# MotorDriver.net
KiCad netlist of a schematic drawn in EAGLE
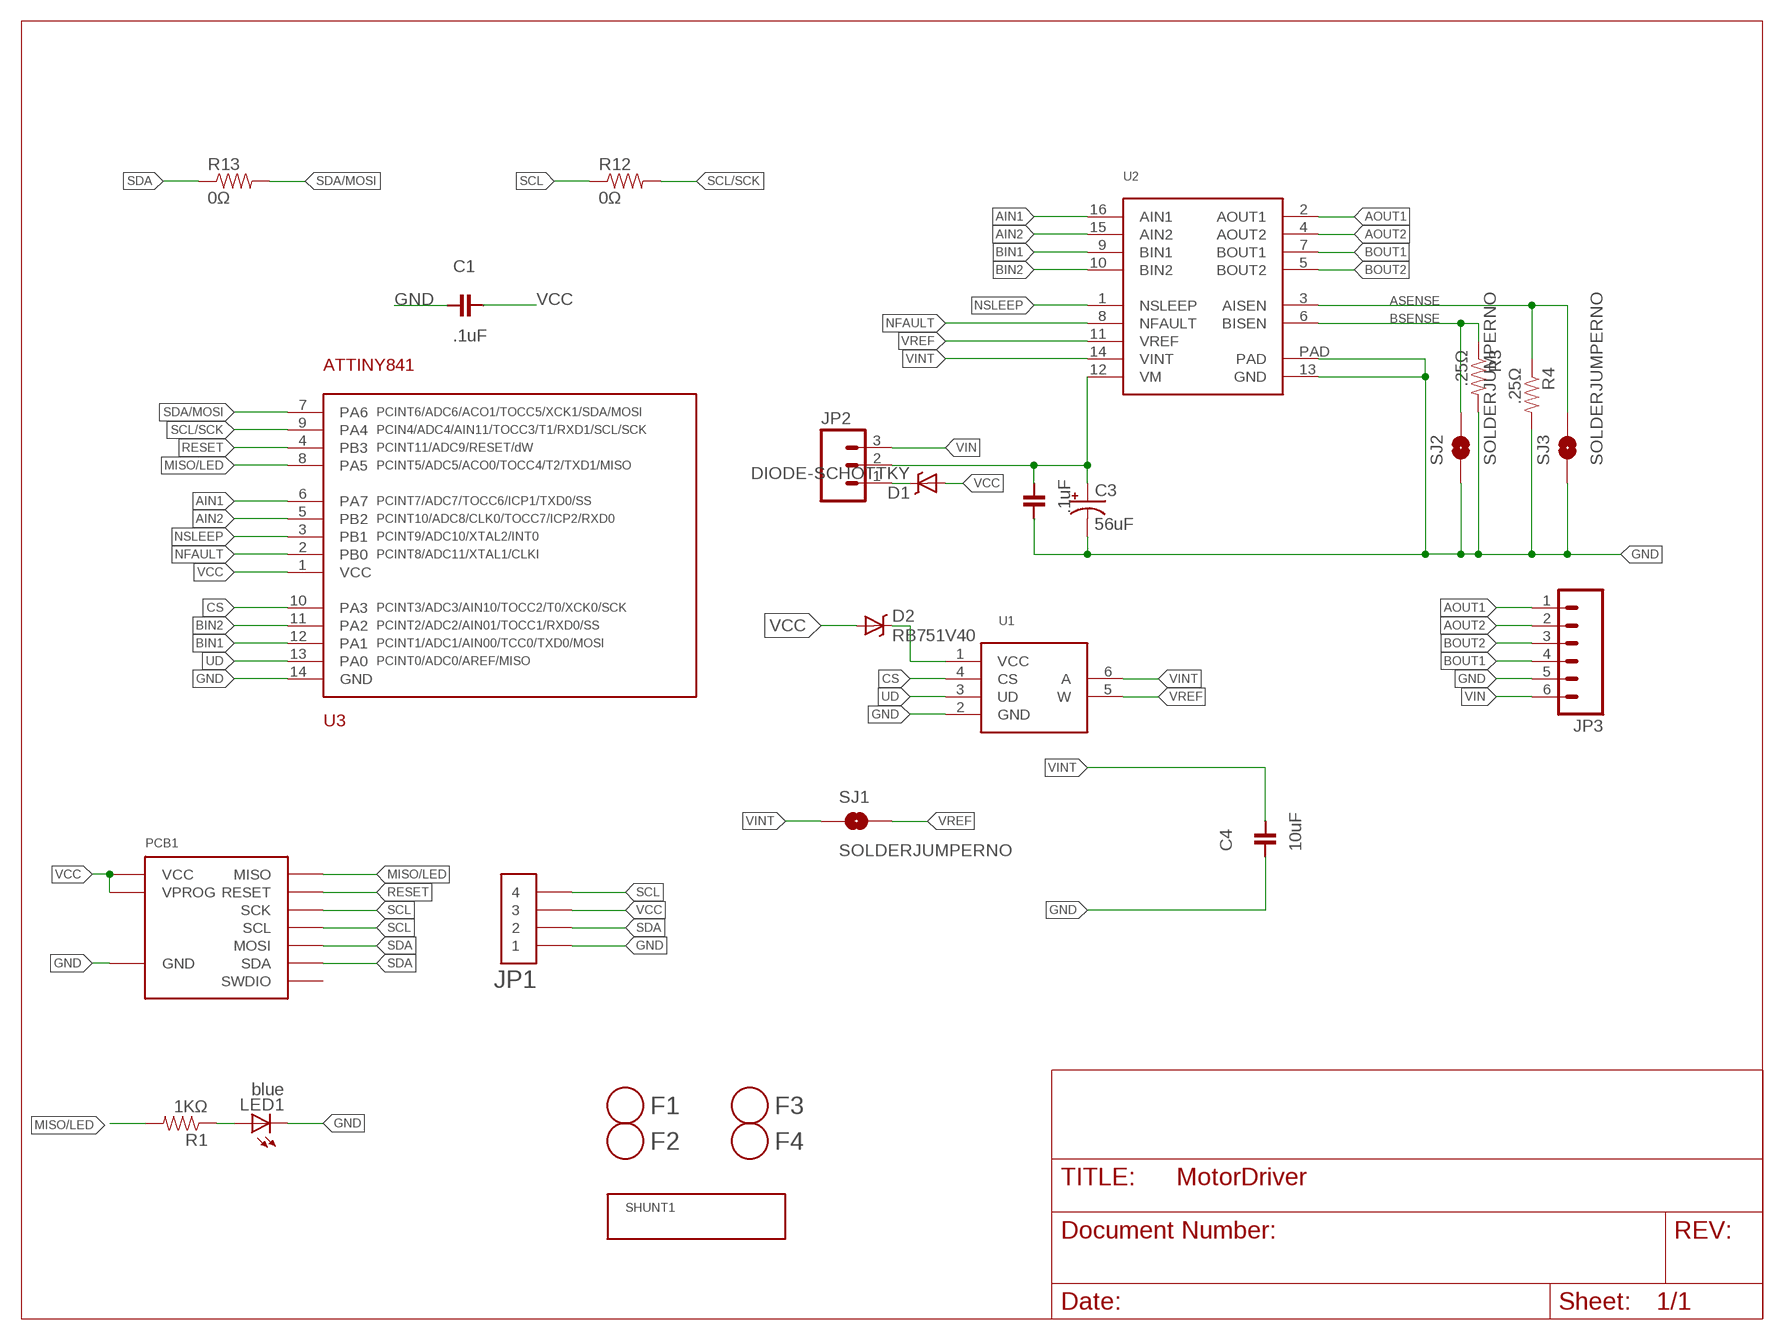
[diagram p0: schematic, sheet 1]

(export (version "E")
  (design (tool "Eeschema 10.0.6"))
  (components
    (comp (ref "C1")
      (value ".1uF")
      (footprint "eagle-import:0603")
      (fields (field (name "PARTNUM") "C0603C104K5RACTU"))
      (libsource (lib "eagle-import") (part "CAPACITOR-.1UF"))
    )
    (comp (ref "C2")
      (value ".1uF")
      (footprint "eagle-import:0603")
      (fields (field (name "PARTNUM") "C0603C104K5RACTU"))
      (libsource (lib "eagle-import") (part "CAPACITOR-.1UF"))
    )
    (comp (ref "C3")
      (value "56uF")
      (footprint "eagle-import:PANASONIC_D")
      (fields (field (name "PARTNUM") "EMVA250ADA560MF55G"))
      (libsource (lib "eagle-import") (part "CAPACITOR-POL-56UF-25V"))
    )
    (comp (ref "C4")
      (value "10uF")
      (footprint "eagle-import:0603")
      (fields (field (name "PARTNUM") "GRM188R61C106MA73D"))
      (libsource (lib "eagle-import") (part "CAPACITOR-10UF"))
    )
    (comp (ref "D1")
      (value "DIODE-SCHOTTKY")
      (footprint "eagle-import:SMP")
      (fields (field (name "PARTNUM") "SS3P3-M3/84A"))
      (libsource (lib "eagle-import") (part "DIODE-SCHOTTKY"))
    )
    (comp (ref "D2")
      (value "RB751V40")
      (footprint "eagle-import:SOD-323")
      (fields (field (name "PARTNUM") "BAT60A") (field (name "PARTNUM_1") "RB751V40"))
      (libsource (lib "eagle-import") (part "DIODE-SCHOTTKY-BAT60A"))
    )
    (comp (ref "F1")
      (value "FIDUCIAL")
      (footprint "eagle-import:FIDUCIAL_1MM")
      (libsource (lib "eagle-import") (part "FIDUCIAL"))
    )
    (comp (ref "F2")
      (value "FIDUCIAL")
      (footprint "eagle-import:FIDUCIAL_1MM")
      (libsource (lib "eagle-import") (part "FIDUCIAL"))
    )
    (comp (ref "F3")
      (value "FIDUCIAL")
      (footprint "eagle-import:FIDUCIAL_1MM")
      (libsource (lib "eagle-import") (part "FIDUCIAL"))
    )
    (comp (ref "F4")
      (value "FIDUCIAL")
      (footprint "eagle-import:FIDUCIAL_1MM")
      (libsource (lib "eagle-import") (part "FIDUCIAL"))
    )
    (comp (ref "JP1")
      (value "HEADER-1X4-AMPMODU")
      (footprint "eagle-import:AMPMODU-4P")
      (fields (field (name "PARTNUM") "147721-3"))
      (libsource (lib "eagle-import") (part "HEADER-1X4-AMPMODU"))
    )
    (comp (ref "JP2")
      (value "M03LOCK_NO_SILK")
      (footprint "eagle-import:1X03_LOCK_NO_SILK")
      (fields (field (name "PARTNUM") "M20-9990346"))
      (libsource (lib "eagle-import") (part "M03LOCK_NO_SILK"))
    )
    (comp (ref "JP3")
      (value "M063.5MM-6")
      (footprint "eagle-import:SCREWTERMINAL-3.5MM-6")
      (fields (field (name "PARTNUM") "OSTTE060104"))
      (libsource (lib "eagle-import") (part "M063.5MM-6"))
    )
    (comp (ref "LED1")
      (value "blue")
      (footprint "eagle-import:0805-LED")
      (fields (field (name "PARTNUM") "LTST-C171TBKT"))
      (libsource (lib "eagle-import") (part "LED-0805-BLUE"))
    )
    (comp (ref "PCB1")
      (value "DEVICE-PCB")
      (footprint "eagle-import:DEVICE-PCB")
      (fields (field (name "PARTNUM") "Motor Driver PCB"))
      (libsource (lib "eagle-import") (part "DEVICE-PCB"))
    )
    (comp (ref "R1")
      (value "1KΩ")
      (footprint "eagle-import:0603")
      (fields (field (name "PARTNUM") "ERJ-3EKF1001V"))
      (libsource (lib "eagle-import") (part "RESISTOR-1KΩ"))
    )
    (comp (ref "R3")
      (value ".25Ω")
      (footprint "eagle-import:R2010")
      (fields (field (name "PARTNUM") "CSRN2010FKR250"))
      (libsource (lib "eagle-import") (part "RESISTOR2010"))
    )
    (comp (ref "R4")
      (value ".25Ω")
      (footprint "eagle-import:R2010")
      (fields (field (name "PARTNUM") "CSRN2010FKR250"))
      (libsource (lib "eagle-import") (part "RESISTOR2010"))
    )
    (comp (ref "R12")
      (value "0Ω")
      (footprint "eagle-import:0603")
      (fields (field (name "PARTNUM") "ERJ-3GEY0R00V"))
      (libsource (lib "eagle-import") (part "RESISTOR-0Ω"))
    )
    (comp (ref "R13")
      (value "0Ω")
      (footprint "eagle-import:0603")
      (fields (field (name "PARTNUM") "ERJ-3GEY0R00V"))
      (libsource (lib "eagle-import") (part "RESISTOR-0Ω"))
    )
    (comp (ref "SJ1")
      (value "SOLDERJUMPERNO")
      (footprint "eagle-import:SJ_2S-NO")
      (libsource (lib "eagle-import") (part "SOLDERJUMPERNO"))
    )
    (comp (ref "SJ2")
      (value "SOLDERJUMPERNO")
      (footprint "eagle-import:SJ_2S-NO")
      (libsource (lib "eagle-import") (part "SOLDERJUMPERNO"))
    )
    (comp (ref "SJ3")
      (value "SOLDERJUMPERNO")
      (footprint "eagle-import:SJ_2S-NO")
      (libsource (lib "eagle-import") (part "SOLDERJUMPERNO"))
    )
    (comp (ref "U1")
      (value "MCP4013")
      (footprint "eagle-import:SOT-23-6")
      (fields (field (name "PARTNUM") "MCP4013T-503E/CH"))
      (libsource (lib "eagle-import") (part "MCP4013"))
    )
    (comp (ref "U2")
      (value "DRV8848")
      (footprint "eagle-import:HTSSOP-16")
      (fields (field (name "PARTNUM") "DRV8848PWP"))
      (libsource (lib "eagle-import") (part "DRV8848"))
    )
    (comp (ref "U3")
      (value "ATTINY841")
      (footprint "eagle-import:SOIC-14")
      (fields (field (name "PARTNUM") "ATTINY841-SSUR"))
      (libsource (lib "eagle-import") (part "ATTINY841"))
    )
  )
  (nets
    (net (code "1") (name "/ASENSE") (class "Default")
      (node (ref "R4") (pin "1") (pinfunction "1_1") (pintype "passive"))
      (node (ref "SJ3") (pin "2") (pinfunction "2_2") (pintype "passive"))
      (node (ref "U2") (pin "3") (pinfunction "AISEN_3") (pintype "bidirectional"))
    )
    (net (code "2") (name "/BSENSE") (class "Default")
      (node (ref "R3") (pin "1") (pinfunction "1_1") (pintype "passive"))
      (node (ref "SJ2") (pin "2") (pinfunction "2_2") (pintype "passive"))
      (node (ref "U2") (pin "6") (pinfunction "BISEN_6") (pintype "bidirectional"))
    )
    (net (code "3") (name "AIN1") (class "Default")
      (node (ref "U2") (pin "16") (pinfunction "AIN1_16") (pintype "bidirectional"))
      (node (ref "U3") (pin "6") (pinfunction "PA7_6") (pintype "bidirectional"))
    )
    (net (code "4") (name "AIN2") (class "Default")
      (node (ref "U2") (pin "15") (pinfunction "AIN2_15") (pintype "bidirectional"))
      (node (ref "U3") (pin "5") (pinfunction "PB2_5") (pintype "bidirectional"))
    )
    (net (code "5") (name "AOUT1") (class "Default")
      (node (ref "JP3") (pin "1") (pinfunction "1_1") (pintype "passive"))
      (node (ref "U2") (pin "2") (pinfunction "AOUT1_2") (pintype "bidirectional"))
    )
    (net (code "6") (name "AOUT2") (class "Default")
      (node (ref "JP3") (pin "2") (pinfunction "2_2") (pintype "passive"))
      (node (ref "U2") (pin "4") (pinfunction "AOUT2_4") (pintype "bidirectional"))
    )
    (net (code "7") (name "BIN1") (class "Default")
      (node (ref "U2") (pin "9") (pinfunction "BIN1_9") (pintype "bidirectional"))
      (node (ref "U3") (pin "12") (pinfunction "PA1_12") (pintype "bidirectional"))
    )
    (net (code "8") (name "BIN2") (class "Default")
      (node (ref "U2") (pin "10") (pinfunction "BIN2_10") (pintype "bidirectional"))
      (node (ref "U3") (pin "11") (pinfunction "PA2_11") (pintype "bidirectional"))
    )
    (net (code "9") (name "BOUT1") (class "Default")
      (node (ref "JP3") (pin "4") (pinfunction "4_4") (pintype "passive"))
      (node (ref "U2") (pin "7") (pinfunction "BOUT1_7") (pintype "bidirectional"))
    )
    (net (code "10") (name "BOUT2") (class "Default")
      (node (ref "JP3") (pin "3") (pinfunction "3_3") (pintype "passive"))
      (node (ref "U2") (pin "5") (pinfunction "BOUT2_5") (pintype "bidirectional"))
    )
    (net (code "11") (name "CS") (class "Default")
      (node (ref "U1") (pin "4") (pinfunction "CS_4") (pintype "bidirectional"))
      (node (ref "U3") (pin "10") (pinfunction "PA3_10") (pintype "bidirectional"))
    )
    (net (code "12") (name "GND") (class "Default")
      (node (ref "C1") (pin "2") (pinfunction "2_2") (pintype "passive"))
      (node (ref "C2") (pin "2") (pinfunction "2_2") (pintype "passive"))
      (node (ref "C3") (pin "-") (pinfunction "-_-") (pintype "passive"))
      (node (ref "C4") (pin "2") (pinfunction "2_2") (pintype "passive"))
      (node (ref "JP1") (pin "P$1") (pinfunction "1_P$1") (pintype "bidirectional"))
      (node (ref "JP1") (pin "P$2") (pinfunction "1_P$2") (pintype "bidirectional"))
      (node (ref "JP3") (pin "5") (pinfunction "5_5") (pintype "passive"))
      (node (ref "LED1") (pin "C") (pinfunction "C_C") (pintype "passive"))
      (node (ref "PCB1") (pin "GND") (pinfunction "GND_GND") (pintype "bidirectional"))
      (node (ref "R3") (pin "2") (pinfunction "2_2") (pintype "passive"))
      (node (ref "R4") (pin "2") (pinfunction "2_2") (pintype "passive"))
      (node (ref "SJ2") (pin "1") (pinfunction "1_1") (pintype "passive"))
      (node (ref "SJ3") (pin "1") (pinfunction "1_1") (pintype "passive"))
      (node (ref "U1") (pin "2") (pinfunction "GND_2") (pintype "bidirectional"))
      (node (ref "U2") (pin "13") (pinfunction "GND_13") (pintype "bidirectional"))
      (node (ref "U2") (pin "PAD") (pinfunction "PAD_PAD") (pintype "bidirectional"))
      (node (ref "U3") (pin "14") (pinfunction "GND_14") (pintype "bidirectional"))
    )
    (net (code "13") (name "MISO{slash}LED") (class "Default")
      (node (ref "PCB1") (pin "MISO") (pinfunction "MISO_MISO") (pintype "bidirectional"))
      (node (ref "R1") (pin "2") (pinfunction "2_2") (pintype "passive"))
      (node (ref "U3") (pin "8") (pinfunction "PA5_8") (pintype "bidirectional"))
    )
    (net (code "14") (name "NFAULT") (class "Default")
      (node (ref "U2") (pin "8") (pinfunction "NFAULT_8") (pintype "bidirectional"))
      (node (ref "U3") (pin "2") (pinfunction "PB0_2") (pintype "bidirectional"))
    )
    (net (code "15") (name "NSLEEP") (class "Default")
      (node (ref "U2") (pin "1") (pinfunction "NSLEEP_1") (pintype "bidirectional"))
      (node (ref "U3") (pin "3") (pinfunction "PB1_3") (pintype "bidirectional"))
    )
    (net (code "16") (name "Net-(D1-PadC)") (class "Default")
      (node (ref "D1") (pin "C") (pinfunction "C_C") (pintype "passive"))
      (node (ref "JP2") (pin "1") (pinfunction "1_1") (pintype "passive"))
    )
    (net (code "17") (name "Net-(LED1-PadA)") (class "Default")
      (node (ref "LED1") (pin "A") (pinfunction "A_A") (pintype "passive"))
      (node (ref "R1") (pin "1") (pinfunction "1_1") (pintype "passive"))
    )
    (net (code "18") (name "Net-(U1-VCC)") (class "Default")
      (node (ref "D2") (pin "C") (pinfunction "C_C") (pintype "passive"))
      (node (ref "U1") (pin "1") (pinfunction "VCC_1") (pintype "bidirectional"))
    )
    (net (code "19") (name "Net-(U2-VM)") (class "Default")
      (node (ref "C2") (pin "1") (pinfunction "1_1") (pintype "passive"))
      (node (ref "C3") (pin "+") (pinfunction "+_+") (pintype "passive"))
      (node (ref "JP2") (pin "2") (pinfunction "2_2") (pintype "passive"))
      (node (ref "U2") (pin "12") (pinfunction "VM_12") (pintype "bidirectional"))
    )
    (net (code "20") (name "RESET") (class "Default")
      (node (ref "PCB1") (pin "RESET") (pinfunction "RESET_RESET") (pintype "bidirectional"))
      (node (ref "U3") (pin "4") (pinfunction "PB3_4") (pintype "bidirectional"))
    )
    (net (code "21") (name "SCL") (class "Default")
      (node (ref "JP1") (pin "P$7") (pinfunction "4_P$7") (pintype "bidirectional"))
      (node (ref "JP1") (pin "P$8") (pinfunction "4_P$8") (pintype "bidirectional"))
      (node (ref "PCB1") (pin "CLK") (pinfunction "SCK_CLK") (pintype "bidirectional"))
      (node (ref "PCB1") (pin "SCL") (pinfunction "SCL_SCL") (pintype "bidirectional"))
      (node (ref "R12") (pin "1") (pinfunction "1_1") (pintype "passive"))
    )
    (net (code "22") (name "SCL{slash}SCK") (class "Default")
      (node (ref "R12") (pin "2") (pinfunction "2_2") (pintype "passive"))
      (node (ref "U3") (pin "9") (pinfunction "PA4_9") (pintype "bidirectional"))
    )
    (net (code "23") (name "SDA") (class "Default")
      (node (ref "JP1") (pin "P$3") (pinfunction "2_P$3") (pintype "bidirectional"))
      (node (ref "JP1") (pin "P$4") (pinfunction "2_P$4") (pintype "bidirectional"))
      (node (ref "PCB1") (pin "MOSI") (pinfunction "MOSI_MOSI") (pintype "bidirectional"))
      (node (ref "PCB1") (pin "SDA") (pinfunction "SDA_SDA") (pintype "bidirectional"))
      (node (ref "R13") (pin "1") (pinfunction "1_1") (pintype "passive"))
    )
    (net (code "24") (name "SDA{slash}MOSI") (class "Default")
      (node (ref "R13") (pin "2") (pinfunction "2_2") (pintype "passive"))
      (node (ref "U3") (pin "7") (pinfunction "PA6_7") (pintype "bidirectional"))
    )
    (net (code "25") (name "UD") (class "Default")
      (node (ref "U1") (pin "3") (pinfunction "UD_3") (pintype "bidirectional"))
      (node (ref "U3") (pin "13") (pinfunction "PA0_13") (pintype "bidirectional"))
    )
    (net (code "26") (name "VCC") (class "Default")
      (node (ref "C1") (pin "1") (pinfunction "1_1") (pintype "passive"))
      (node (ref "D1") (pin "A") (pinfunction "A_A") (pintype "passive"))
      (node (ref "D2") (pin "A") (pinfunction "A_A") (pintype "passive"))
      (node (ref "JP1") (pin "P$5") (pinfunction "3_P$5") (pintype "bidirectional"))
      (node (ref "JP1") (pin "P$6") (pinfunction "3_P$6") (pintype "bidirectional"))
      (node (ref "PCB1") (pin "VCC") (pinfunction "VCC_VCC") (pintype "bidirectional"))
      (node (ref "PCB1") (pin "VPROG") (pinfunction "VPROG_VPROG") (pintype "bidirectional"))
      (node (ref "U3") (pin "1") (pinfunction "VCC_1") (pintype "bidirectional"))
    )
    (net (code "27") (name "VIN") (class "Default")
      (node (ref "JP2") (pin "3") (pinfunction "3_3") (pintype "passive"))
      (node (ref "JP3") (pin "6") (pinfunction "6_6") (pintype "passive"))
    )
    (net (code "28") (name "VINT") (class "Default")
      (node (ref "C4") (pin "1") (pinfunction "1_1") (pintype "passive"))
      (node (ref "SJ1") (pin "1") (pinfunction "1_1") (pintype "passive"))
      (node (ref "U1") (pin "6") (pinfunction "A_6") (pintype "bidirectional"))
      (node (ref "U2") (pin "14") (pinfunction "VINT_14") (pintype "bidirectional"))
    )
    (net (code "29") (name "VREF") (class "Default")
      (node (ref "SJ1") (pin "2") (pinfunction "2_2") (pintype "passive"))
      (node (ref "U1") (pin "5") (pinfunction "W_5") (pintype "bidirectional"))
      (node (ref "U2") (pin "11") (pinfunction "VREF_11") (pintype "bidirectional"))
    )
    (net (code "30") (name "unconnected-(PCB1-PadSWDIO)") (class "Default")
      (node (ref "PCB1") (pin "SWDIO") (pinfunction "SWDIO_SWDIO") (pintype "bidirectional"))
    )
  )
)
